# LED_Array.net
KiCad netlist of a schematic drawn in Altium Designer
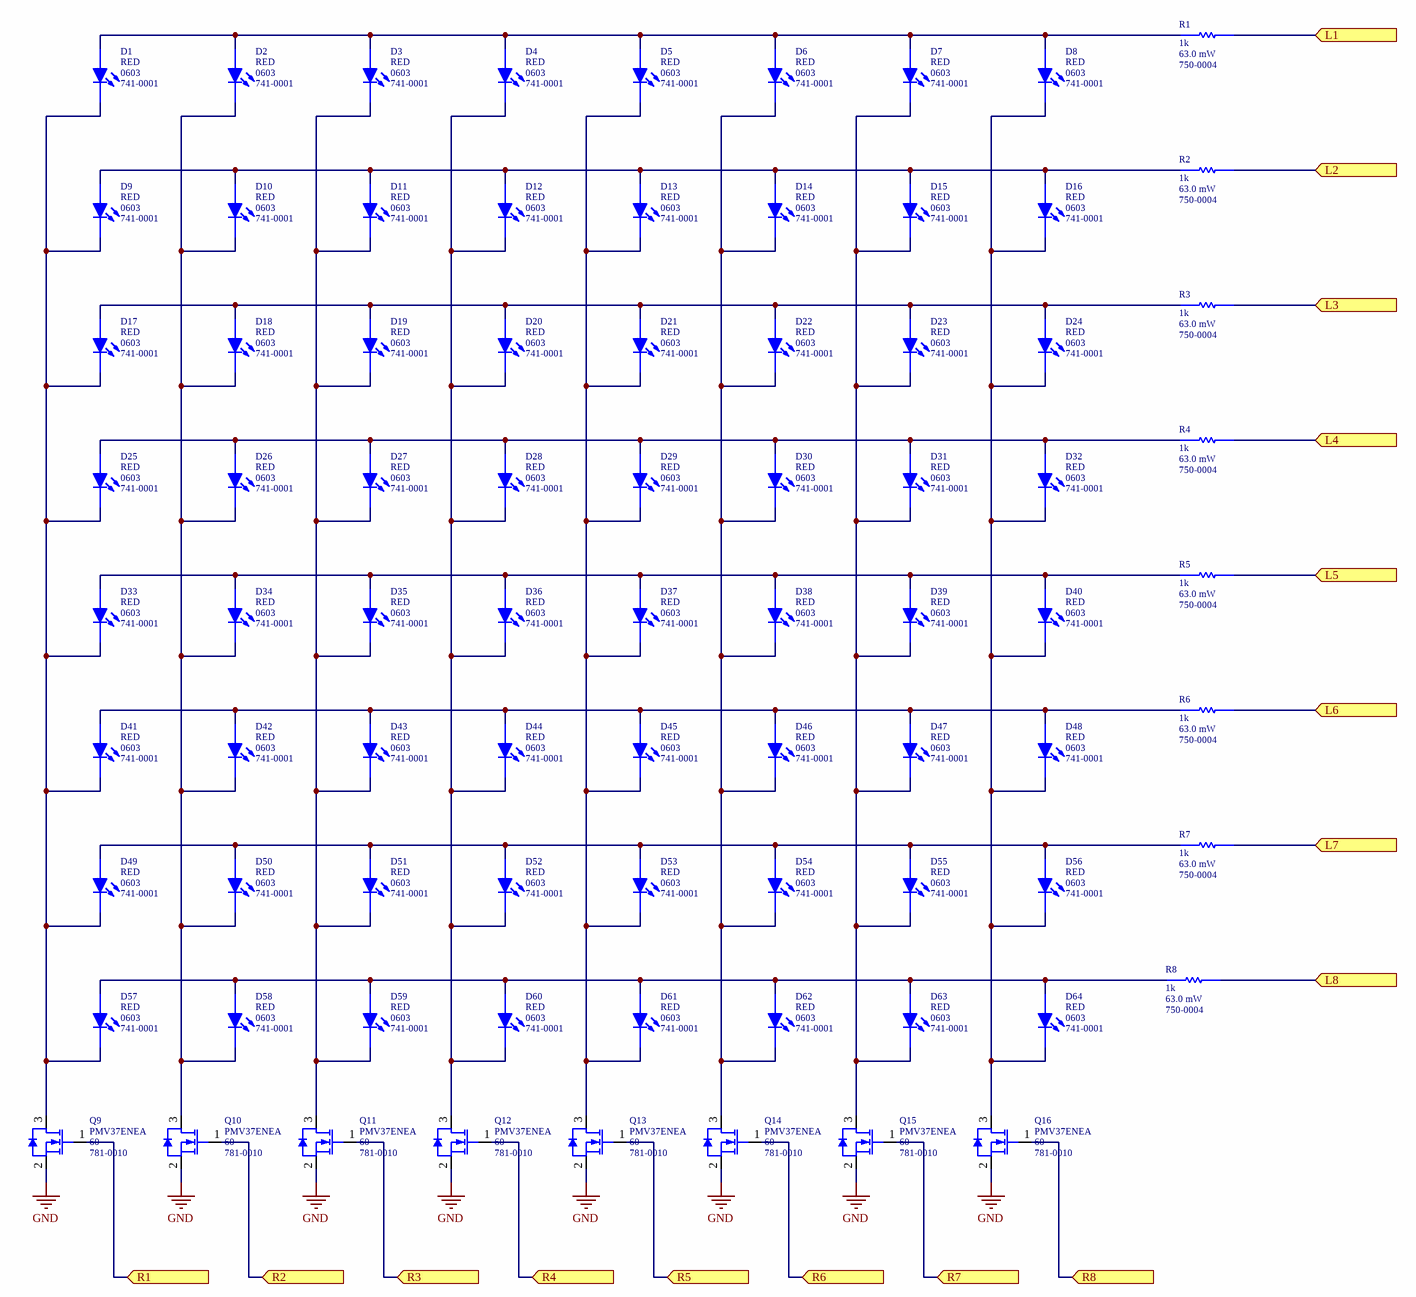
[diagram p0: LED Array.SchDoc]

(export (version "E")
  (design (tool "Eeschema 10.0.6"))
  (components
    (comp (ref "D1")
      (value "RED")
      (footprint "LED0603-IPC-MD")
      (description "LED RED 0603 2V 20mA 75mW")
      (fields
        (field (name "PACKAGE") "0603")
        (field (name "PART NUMBER") "741-0001")
        (field (name "MPN") "VLMS1300-GS08")
        (field (name "MANUFACTURER") "VISHAY")
      )
      (libsource (lib "rnlib2") (part "LED"))
    )
    (comp (ref "D2")
      (value "RED")
      (footprint "LED0603-IPC-MD")
      (description "LED RED 0603 2V 20mA 75mW")
      (fields
        (field (name "PACKAGE") "0603")
        (field (name "PART NUMBER") "741-0001")
        (field (name "MPN") "VLMS1300-GS08")
        (field (name "MANUFACTURER") "VISHAY")
      )
      (libsource (lib "rnlib2") (part "LED"))
    )
    (comp (ref "D3")
      (value "RED")
      (footprint "LED0603-IPC-MD")
      (description "LED RED 0603 2V 20mA 75mW")
      (fields
        (field (name "PACKAGE") "0603")
        (field (name "PART NUMBER") "741-0001")
        (field (name "MPN") "VLMS1300-GS08")
        (field (name "MANUFACTURER") "VISHAY")
      )
      (libsource (lib "rnlib2") (part "LED"))
    )
    (comp (ref "D4")
      (value "RED")
      (footprint "LED0603-IPC-MD")
      (description "LED RED 0603 2V 20mA 75mW")
      (fields
        (field (name "PACKAGE") "0603")
        (field (name "PART NUMBER") "741-0001")
        (field (name "MPN") "VLMS1300-GS08")
        (field (name "MANUFACTURER") "VISHAY")
      )
      (libsource (lib "rnlib2") (part "LED"))
    )
    (comp (ref "D5")
      (value "RED")
      (footprint "LED0603-IPC-MD")
      (description "LED RED 0603 2V 20mA 75mW")
      (fields
        (field (name "PACKAGE") "0603")
        (field (name "PART NUMBER") "741-0001")
        (field (name "MPN") "VLMS1300-GS08")
        (field (name "MANUFACTURER") "VISHAY")
      )
      (libsource (lib "rnlib2") (part "LED"))
    )
    (comp (ref "D6")
      (value "RED")
      (footprint "LED0603-IPC-MD")
      (description "LED RED 0603 2V 20mA 75mW")
      (fields
        (field (name "PACKAGE") "0603")
        (field (name "PART NUMBER") "741-0001")
        (field (name "MPN") "VLMS1300-GS08")
        (field (name "MANUFACTURER") "VISHAY")
      )
      (libsource (lib "rnlib2") (part "LED"))
    )
    (comp (ref "D7")
      (value "RED")
      (footprint "LED0603-IPC-MD")
      (description "LED RED 0603 2V 20mA 75mW")
      (fields
        (field (name "PACKAGE") "0603")
        (field (name "PART NUMBER") "741-0001")
        (field (name "MPN") "VLMS1300-GS08")
        (field (name "MANUFACTURER") "VISHAY")
      )
      (libsource (lib "rnlib2") (part "LED"))
    )
    (comp (ref "D8")
      (value "RED")
      (footprint "LED0603-IPC-MD")
      (description "LED RED 0603 2V 20mA 75mW")
      (fields
        (field (name "PACKAGE") "0603")
        (field (name "PART NUMBER") "741-0001")
        (field (name "MPN") "VLMS1300-GS08")
        (field (name "MANUFACTURER") "VISHAY")
      )
      (libsource (lib "rnlib2") (part "LED"))
    )
    (comp (ref "D9")
      (value "RED")
      (footprint "LED0603-IPC-MD")
      (description "LED RED 0603 2V 20mA 75mW")
      (fields
        (field (name "PACKAGE") "0603")
        (field (name "PART NUMBER") "741-0001")
        (field (name "MPN") "VLMS1300-GS08")
        (field (name "MANUFACTURER") "VISHAY")
      )
      (libsource (lib "rnlib2") (part "LED"))
    )
    (comp (ref "D10")
      (value "RED")
      (footprint "LED0603-IPC-MD")
      (description "LED RED 0603 2V 20mA 75mW")
      (fields
        (field (name "PACKAGE") "0603")
        (field (name "PART NUMBER") "741-0001")
        (field (name "MPN") "VLMS1300-GS08")
        (field (name "MANUFACTURER") "VISHAY")
      )
      (libsource (lib "rnlib2") (part "LED"))
    )
    (comp (ref "D11")
      (value "RED")
      (footprint "LED0603-IPC-MD")
      (description "LED RED 0603 2V 20mA 75mW")
      (fields
        (field (name "PACKAGE") "0603")
        (field (name "PART NUMBER") "741-0001")
        (field (name "MPN") "VLMS1300-GS08")
        (field (name "MANUFACTURER") "VISHAY")
      )
      (libsource (lib "rnlib2") (part "LED"))
    )
    (comp (ref "D12")
      (value "RED")
      (footprint "LED0603-IPC-MD")
      (description "LED RED 0603 2V 20mA 75mW")
      (fields
        (field (name "PACKAGE") "0603")
        (field (name "PART NUMBER") "741-0001")
        (field (name "MPN") "VLMS1300-GS08")
        (field (name "MANUFACTURER") "VISHAY")
      )
      (libsource (lib "rnlib2") (part "LED"))
    )
    (comp (ref "D13")
      (value "RED")
      (footprint "LED0603-IPC-MD")
      (description "LED RED 0603 2V 20mA 75mW")
      (fields
        (field (name "PACKAGE") "0603")
        (field (name "PART NUMBER") "741-0001")
        (field (name "MPN") "VLMS1300-GS08")
        (field (name "MANUFACTURER") "VISHAY")
      )
      (libsource (lib "rnlib2") (part "LED"))
    )
    (comp (ref "D14")
      (value "RED")
      (footprint "LED0603-IPC-MD")
      (description "LED RED 0603 2V 20mA 75mW")
      (fields
        (field (name "PACKAGE") "0603")
        (field (name "PART NUMBER") "741-0001")
        (field (name "MPN") "VLMS1300-GS08")
        (field (name "MANUFACTURER") "VISHAY")
      )
      (libsource (lib "rnlib2") (part "LED"))
    )
    (comp (ref "D15")
      (value "RED")
      (footprint "LED0603-IPC-MD")
      (description "LED RED 0603 2V 20mA 75mW")
      (fields
        (field (name "PACKAGE") "0603")
        (field (name "PART NUMBER") "741-0001")
        (field (name "MPN") "VLMS1300-GS08")
        (field (name "MANUFACTURER") "VISHAY")
      )
      (libsource (lib "rnlib2") (part "LED"))
    )
    (comp (ref "D16")
      (value "RED")
      (footprint "LED0603-IPC-MD")
      (description "LED RED 0603 2V 20mA 75mW")
      (fields
        (field (name "PACKAGE") "0603")
        (field (name "PART NUMBER") "741-0001")
        (field (name "MPN") "VLMS1300-GS08")
        (field (name "MANUFACTURER") "VISHAY")
      )
      (libsource (lib "rnlib2") (part "LED"))
    )
    (comp (ref "D17")
      (value "RED")
      (footprint "LED0603-IPC-MD")
      (description "LED RED 0603 2V 20mA 75mW")
      (fields
        (field (name "PACKAGE") "0603")
        (field (name "PART NUMBER") "741-0001")
        (field (name "MPN") "VLMS1300-GS08")
        (field (name "MANUFACTURER") "VISHAY")
      )
      (libsource (lib "rnlib2") (part "LED"))
    )
    (comp (ref "D18")
      (value "RED")
      (footprint "LED0603-IPC-MD")
      (description "LED RED 0603 2V 20mA 75mW")
      (fields
        (field (name "PACKAGE") "0603")
        (field (name "PART NUMBER") "741-0001")
        (field (name "MPN") "VLMS1300-GS08")
        (field (name "MANUFACTURER") "VISHAY")
      )
      (libsource (lib "rnlib2") (part "LED"))
    )
    (comp (ref "D19")
      (value "RED")
      (footprint "LED0603-IPC-MD")
      (description "LED RED 0603 2V 20mA 75mW")
      (fields
        (field (name "PACKAGE") "0603")
        (field (name "PART NUMBER") "741-0001")
        (field (name "MPN") "VLMS1300-GS08")
        (field (name "MANUFACTURER") "VISHAY")
      )
      (libsource (lib "rnlib2") (part "LED"))
    )
    (comp (ref "D20")
      (value "RED")
      (footprint "LED0603-IPC-MD")
      (description "LED RED 0603 2V 20mA 75mW")
      (fields
        (field (name "PACKAGE") "0603")
        (field (name "PART NUMBER") "741-0001")
        (field (name "MPN") "VLMS1300-GS08")
        (field (name "MANUFACTURER") "VISHAY")
      )
      (libsource (lib "rnlib2") (part "LED"))
    )
    (comp (ref "D21")
      (value "RED")
      (footprint "LED0603-IPC-MD")
      (description "LED RED 0603 2V 20mA 75mW")
      (fields
        (field (name "PACKAGE") "0603")
        (field (name "PART NUMBER") "741-0001")
        (field (name "MPN") "VLMS1300-GS08")
        (field (name "MANUFACTURER") "VISHAY")
      )
      (libsource (lib "rnlib2") (part "LED"))
    )
    (comp (ref "D22")
      (value "RED")
      (footprint "LED0603-IPC-MD")
      (description "LED RED 0603 2V 20mA 75mW")
      (fields
        (field (name "PACKAGE") "0603")
        (field (name "PART NUMBER") "741-0001")
        (field (name "MPN") "VLMS1300-GS08")
        (field (name "MANUFACTURER") "VISHAY")
      )
      (libsource (lib "rnlib2") (part "LED"))
    )
    (comp (ref "D23")
      (value "RED")
      (footprint "LED0603-IPC-MD")
      (description "LED RED 0603 2V 20mA 75mW")
      (fields
        (field (name "PACKAGE") "0603")
        (field (name "PART NUMBER") "741-0001")
        (field (name "MPN") "VLMS1300-GS08")
        (field (name "MANUFACTURER") "VISHAY")
      )
      (libsource (lib "rnlib2") (part "LED"))
    )
    (comp (ref "D24")
      (value "RED")
      (footprint "LED0603-IPC-MD")
      (description "LED RED 0603 2V 20mA 75mW")
      (fields
        (field (name "PACKAGE") "0603")
        (field (name "PART NUMBER") "741-0001")
        (field (name "MPN") "VLMS1300-GS08")
        (field (name "MANUFACTURER") "VISHAY")
      )
      (libsource (lib "rnlib2") (part "LED"))
    )
    (comp (ref "D25")
      (value "RED")
      (footprint "LED0603-IPC-MD")
      (description "LED RED 0603 2V 20mA 75mW")
      (fields
        (field (name "PACKAGE") "0603")
        (field (name "PART NUMBER") "741-0001")
        (field (name "MPN") "VLMS1300-GS08")
        (field (name "MANUFACTURER") "VISHAY")
      )
      (libsource (lib "rnlib2") (part "LED"))
    )
    (comp (ref "D26")
      (value "RED")
      (footprint "LED0603-IPC-MD")
      (description "LED RED 0603 2V 20mA 75mW")
      (fields
        (field (name "PACKAGE") "0603")
        (field (name "PART NUMBER") "741-0001")
        (field (name "MPN") "VLMS1300-GS08")
        (field (name "MANUFACTURER") "VISHAY")
      )
      (libsource (lib "rnlib2") (part "LED"))
    )
    (comp (ref "D27")
      (value "RED")
      (footprint "LED0603-IPC-MD")
      (description "LED RED 0603 2V 20mA 75mW")
      (fields
        (field (name "PACKAGE") "0603")
        (field (name "PART NUMBER") "741-0001")
        (field (name "MPN") "VLMS1300-GS08")
        (field (name "MANUFACTURER") "VISHAY")
      )
      (libsource (lib "rnlib2") (part "LED"))
    )
    (comp (ref "D28")
      (value "RED")
      (footprint "LED0603-IPC-MD")
      (description "LED RED 0603 2V 20mA 75mW")
      (fields
        (field (name "PACKAGE") "0603")
        (field (name "PART NUMBER") "741-0001")
        (field (name "MPN") "VLMS1300-GS08")
        (field (name "MANUFACTURER") "VISHAY")
      )
      (libsource (lib "rnlib2") (part "LED"))
    )
    (comp (ref "D29")
      (value "RED")
      (footprint "LED0603-IPC-MD")
      (description "LED RED 0603 2V 20mA 75mW")
      (fields
        (field (name "PACKAGE") "0603")
        (field (name "PART NUMBER") "741-0001")
        (field (name "MPN") "VLMS1300-GS08")
        (field (name "MANUFACTURER") "VISHAY")
      )
      (libsource (lib "rnlib2") (part "LED"))
    )
    (comp (ref "D30")
      (value "RED")
      (footprint "LED0603-IPC-MD")
      (description "LED RED 0603 2V 20mA 75mW")
      (fields
        (field (name "PACKAGE") "0603")
        (field (name "PART NUMBER") "741-0001")
        (field (name "MPN") "VLMS1300-GS08")
        (field (name "MANUFACTURER") "VISHAY")
      )
      (libsource (lib "rnlib2") (part "LED"))
    )
    (comp (ref "D31")
      (value "RED")
      (footprint "LED0603-IPC-MD")
      (description "LED RED 0603 2V 20mA 75mW")
      (fields
        (field (name "PACKAGE") "0603")
        (field (name "PART NUMBER") "741-0001")
        (field (name "MPN") "VLMS1300-GS08")
        (field (name "MANUFACTURER") "VISHAY")
      )
      (libsource (lib "rnlib2") (part "LED"))
    )
    (comp (ref "D32")
      (value "RED")
      (footprint "LED0603-IPC-MD")
      (description "LED RED 0603 2V 20mA 75mW")
      (fields
        (field (name "PACKAGE") "0603")
        (field (name "PART NUMBER") "741-0001")
        (field (name "MPN") "VLMS1300-GS08")
        (field (name "MANUFACTURER") "VISHAY")
      )
      (libsource (lib "rnlib2") (part "LED"))
    )
    (comp (ref "D33")
      (value "RED")
      (footprint "LED0603-IPC-MD")
      (description "LED RED 0603 2V 20mA 75mW")
      (fields
        (field (name "PACKAGE") "0603")
        (field (name "PART NUMBER") "741-0001")
        (field (name "MPN") "VLMS1300-GS08")
        (field (name "MANUFACTURER") "VISHAY")
      )
      (libsource (lib "rnlib2") (part "LED"))
    )
    (comp (ref "D34")
      (value "RED")
      (footprint "LED0603-IPC-MD")
      (description "LED RED 0603 2V 20mA 75mW")
      (fields
        (field (name "PACKAGE") "0603")
        (field (name "PART NUMBER") "741-0001")
        (field (name "MPN") "VLMS1300-GS08")
        (field (name "MANUFACTURER") "VISHAY")
      )
      (libsource (lib "rnlib2") (part "LED"))
    )
    (comp (ref "D35")
      (value "RED")
      (footprint "LED0603-IPC-MD")
      (description "LED RED 0603 2V 20mA 75mW")
      (fields
        (field (name "PACKAGE") "0603")
        (field (name "PART NUMBER") "741-0001")
        (field (name "MPN") "VLMS1300-GS08")
        (field (name "MANUFACTURER") "VISHAY")
      )
      (libsource (lib "rnlib2") (part "LED"))
    )
    (comp (ref "D36")
      (value "RED")
      (footprint "LED0603-IPC-MD")
      (description "LED RED 0603 2V 20mA 75mW")
      (fields
        (field (name "PACKAGE") "0603")
        (field (name "PART NUMBER") "741-0001")
        (field (name "MPN") "VLMS1300-GS08")
        (field (name "MANUFACTURER") "VISHAY")
      )
      (libsource (lib "rnlib2") (part "LED"))
    )
    (comp (ref "D37")
      (value "RED")
      (footprint "LED0603-IPC-MD")
      (description "LED RED 0603 2V 20mA 75mW")
      (fields
        (field (name "PACKAGE") "0603")
        (field (name "PART NUMBER") "741-0001")
        (field (name "MPN") "VLMS1300-GS08")
        (field (name "MANUFACTURER") "VISHAY")
      )
      (libsource (lib "rnlib2") (part "LED"))
    )
    (comp (ref "D38")
      (value "RED")
      (footprint "LED0603-IPC-MD")
      (description "LED RED 0603 2V 20mA 75mW")
      (fields
        (field (name "PACKAGE") "0603")
        (field (name "PART NUMBER") "741-0001")
        (field (name "MPN") "VLMS1300-GS08")
        (field (name "MANUFACTURER") "VISHAY")
      )
      (libsource (lib "rnlib2") (part "LED"))
    )
    (comp (ref "D39")
      (value "RED")
      (footprint "LED0603-IPC-MD")
      (description "LED RED 0603 2V 20mA 75mW")
      (fields
        (field (name "PACKAGE") "0603")
        (field (name "PART NUMBER") "741-0001")
        (field (name "MPN") "VLMS1300-GS08")
        (field (name "MANUFACTURER") "VISHAY")
      )
      (libsource (lib "rnlib2") (part "LED"))
    )
    (comp (ref "D40")
      (value "RED")
      (footprint "LED0603-IPC-MD")
      (description "LED RED 0603 2V 20mA 75mW")
      (fields
        (field (name "PACKAGE") "0603")
        (field (name "PART NUMBER") "741-0001")
        (field (name "MPN") "VLMS1300-GS08")
        (field (name "MANUFACTURER") "VISHAY")
      )
      (libsource (lib "rnlib2") (part "LED"))
    )
    (comp (ref "D41")
      (value "RED")
      (footprint "LED0603-IPC-MD")
      (description "LED RED 0603 2V 20mA 75mW")
      (fields
        (field (name "PACKAGE") "0603")
        (field (name "PART NUMBER") "741-0001")
        (field (name "MPN") "VLMS1300-GS08")
        (field (name "MANUFACTURER") "VISHAY")
      )
      (libsource (lib "rnlib2") (part "LED"))
    )
    (comp (ref "D42")
      (value "RED")
      (footprint "LED0603-IPC-MD")
      (description "LED RED 0603 2V 20mA 75mW")
      (fields
        (field (name "PACKAGE") "0603")
        (field (name "PART NUMBER") "741-0001")
        (field (name "MPN") "VLMS1300-GS08")
        (field (name "MANUFACTURER") "VISHAY")
      )
      (libsource (lib "rnlib2") (part "LED"))
    )
    (comp (ref "D43")
      (value "RED")
      (footprint "LED0603-IPC-MD")
      (description "LED RED 0603 2V 20mA 75mW")
      (fields
        (field (name "PACKAGE") "0603")
        (field (name "PART NUMBER") "741-0001")
        (field (name "MPN") "VLMS1300-GS08")
        (field (name "MANUFACTURER") "VISHAY")
      )
      (libsource (lib "rnlib2") (part "LED"))
    )
    (comp (ref "D44")
      (value "RED")
      (footprint "LED0603-IPC-MD")
      (description "LED RED 0603 2V 20mA 75mW")
      (fields
        (field (name "PACKAGE") "0603")
        (field (name "PART NUMBER") "741-0001")
        (field (name "MPN") "VLMS1300-GS08")
        (field (name "MANUFACTURER") "VISHAY")
      )
      (libsource (lib "rnlib2") (part "LED"))
    )
    (comp (ref "D45")
      (value "RED")
      (footprint "LED0603-IPC-MD")
      (description "LED RED 0603 2V 20mA 75mW")
      (fields
        (field (name "PACKAGE") "0603")
        (field (name "PART NUMBER") "741-0001")
        (field (name "MPN") "VLMS1300-GS08")
        (field (name "MANUFACTURER") "VISHAY")
      )
      (libsource (lib "rnlib2") (part "LED"))
    )
    (comp (ref "D46")
      (value "RED")
      (footprint "LED0603-IPC-MD")
      (description "LED RED 0603 2V 20mA 75mW")
      (fields
        (field (name "PACKAGE") "0603")
        (field (name "PART NUMBER") "741-0001")
        (field (name "MPN") "VLMS1300-GS08")
        (field (name "MANUFACTURER") "VISHAY")
      )
      (libsource (lib "rnlib2") (part "LED"))
    )
    (comp (ref "D47")
      (value "RED")
      (footprint "LED0603-IPC-MD")
      (description "LED RED 0603 2V 20mA 75mW")
      (fields
        (field (name "PACKAGE") "0603")
        (field (name "PART NUMBER") "741-0001")
        (field (name "MPN") "VLMS1300-GS08")
        (field (name "MANUFACTURER") "VISHAY")
      )
      (libsource (lib "rnlib2") (part "LED"))
    )
    (comp (ref "D48")
      (value "RED")
      (footprint "LED0603-IPC-MD")
      (description "LED RED 0603 2V 20mA 75mW")
      (fields
        (field (name "PACKAGE") "0603")
        (field (name "PART NUMBER") "741-0001")
        (field (name "MPN") "VLMS1300-GS08")
        (field (name "MANUFACTURER") "VISHAY")
      )
      (libsource (lib "rnlib2") (part "LED"))
    )
    (comp (ref "D49")
      (value "RED")
      (footprint "LED0603-IPC-MD")
      (description "LED RED 0603 2V 20mA 75mW")
      (fields
        (field (name "PACKAGE") "0603")
        (field (name "PART NUMBER") "741-0001")
        (field (name "MPN") "VLMS1300-GS08")
        (field (name "MANUFACTURER") "VISHAY")
      )
      (libsource (lib "rnlib2") (part "LED"))
    )
    (comp (ref "D50")
      (value "RED")
      (footprint "LED0603-IPC-MD")
      (description "LED RED 0603 2V 20mA 75mW")
      (fields
        (field (name "PACKAGE") "0603")
        (field (name "PART NUMBER") "741-0001")
        (field (name "MPN") "VLMS1300-GS08")
        (field (name "MANUFACTURER") "VISHAY")
      )
      (libsource (lib "rnlib2") (part "LED"))
    )
    (comp (ref "D51")
      (value "RED")
      (footprint "LED0603-IPC-MD")
      (description "LED RED 0603 2V 20mA 75mW")
      (fields
        (field (name "PACKAGE") "0603")
        (field (name "PART NUMBER") "741-0001")
        (field (name "MPN") "VLMS1300-GS08")
        (field (name "MANUFACTURER") "VISHAY")
      )
      (libsource (lib "rnlib2") (part "LED"))
    )
    (comp (ref "D52")
      (value "RED")
      (footprint "LED0603-IPC-MD")
      (description "LED RED 0603 2V 20mA 75mW")
      (fields
        (field (name "PACKAGE") "0603")
        (field (name "PART NUMBER") "741-0001")
        (field (name "MPN") "VLMS1300-GS08")
        (field (name "MANUFACTURER") "VISHAY")
      )
      (libsource (lib "rnlib2") (part "LED"))
    )
    (comp (ref "D53")
      (value "RED")
      (footprint "LED0603-IPC-MD")
      (description "LED RED 0603 2V 20mA 75mW")
      (fields
        (field (name "PACKAGE") "0603")
        (field (name "PART NUMBER") "741-0001")
        (field (name "MPN") "VLMS1300-GS08")
        (field (name "MANUFACTURER") "VISHAY")
      )
      (libsource (lib "rnlib2") (part "LED"))
    )
    (comp (ref "D54")
      (value "RED")
      (footprint "LED0603-IPC-MD")
      (description "LED RED 0603 2V 20mA 75mW")
      (fields
        (field (name "PACKAGE") "0603")
        (field (name "PART NUMBER") "741-0001")
        (field (name "MPN") "VLMS1300-GS08")
        (field (name "MANUFACTURER") "VISHAY")
      )
      (libsource (lib "rnlib2") (part "LED"))
    )
    (comp (ref "D55")
      (value "RED")
      (footprint "LED0603-IPC-MD")
      (description "LED RED 0603 2V 20mA 75mW")
      (fields
        (field (name "PACKAGE") "0603")
        (field (name "PART NUMBER") "741-0001")
        (field (name "MPN") "VLMS1300-GS08")
        (field (name "MANUFACTURER") "VISHAY")
      )
      (libsource (lib "rnlib2") (part "LED"))
    )
    (comp (ref "D56")
      (value "RED")
      (footprint "LED0603-IPC-MD")
      (description "LED RED 0603 2V 20mA 75mW")
      (fields
        (field (name "PACKAGE") "0603")
        (field (name "PART NUMBER") "741-0001")
        (field (name "MPN") "VLMS1300-GS08")
        (field (name "MANUFACTURER") "VISHAY")
      )
      (libsource (lib "rnlib2") (part "LED"))
    )
    (comp (ref "D57")
      (value "RED")
      (footprint "LED0603-IPC-MD")
      (description "LED RED 0603 2V 20mA 75mW")
      (fields
        (field (name "PACKAGE") "0603")
        (field (name "PART NUMBER") "741-0001")
        (field (name "MPN") "VLMS1300-GS08")
        (field (name "MANUFACTURER") "VISHAY")
      )
      (libsource (lib "rnlib2") (part "LED"))
    )
    (comp (ref "D58")
      (value "RED")
      (footprint "LED0603-IPC-MD")
      (description "LED RED 0603 2V 20mA 75mW")
      (fields
        (field (name "PACKAGE") "0603")
        (field (name "PART NUMBER") "741-0001")
        (field (name "MPN") "VLMS1300-GS08")
        (field (name "MANUFACTURER") "VISHAY")
      )
      (libsource (lib "rnlib2") (part "LED"))
    )
    (comp (ref "D59")
      (value "RED")
      (footprint "LED0603-IPC-MD")
      (description "LED RED 0603 2V 20mA 75mW")
      (fields
        (field (name "PACKAGE") "0603")
        (field (name "PART NUMBER") "741-0001")
        (field (name "MPN") "VLMS1300-GS08")
        (field (name "MANUFACTURER") "VISHAY")
      )
      (libsource (lib "rnlib2") (part "LED"))
    )
    (comp (ref "D60")
      (value "RED")
      (footprint "LED0603-IPC-MD")
      (description "LED RED 0603 2V 20mA 75mW")
      (fields
        (field (name "PACKAGE") "0603")
        (field (name "PART NUMBER") "741-0001")
        (field (name "MPN") "VLMS1300-GS08")
        (field (name "MANUFACTURER") "VISHAY")
      )
      (libsource (lib "rnlib2") (part "LED"))
    )
    (comp (ref "D61")
      (value "RED")
      (footprint "LED0603-IPC-MD")
      (description "LED RED 0603 2V 20mA 75mW")
      (fields
        (field (name "PACKAGE") "0603")
        (field (name "PART NUMBER") "741-0001")
        (field (name "MPN") "VLMS1300-GS08")
        (field (name "MANUFACTURER") "VISHAY")
      )
      (libsource (lib "rnlib2") (part "LED"))
    )
    (comp (ref "D62")
      (value "RED")
      (footprint "LED0603-IPC-MD")
      (description "LED RED 0603 2V 20mA 75mW")
      (fields
        (field (name "PACKAGE") "0603")
        (field (name "PART NUMBER") "741-0001")
        (field (name "MPN") "VLMS1300-GS08")
        (field (name "MANUFACTURER") "VISHAY")
      )
      (libsource (lib "rnlib2") (part "LED"))
    )
    (comp (ref "D63")
      (value "RED")
      (footprint "LED0603-IPC-MD")
      (description "LED RED 0603 2V 20mA 75mW")
      (fields
        (field (name "PACKAGE") "0603")
        (field (name "PART NUMBER") "741-0001")
        (field (name "MPN") "VLMS1300-GS08")
        (field (name "MANUFACTURER") "VISHAY")
      )
      (libsource (lib "rnlib2") (part "LED"))
    )
    (comp (ref "D64")
      (value "RED")
      (footprint "LED0603-IPC-MD")
      (description "LED RED 0603 2V 20mA 75mW")
      (fields
        (field (name "PACKAGE") "0603")
        (field (name "PART NUMBER") "741-0001")
        (field (name "MPN") "VLMS1300-GS08")
        (field (name "MANUFACTURER") "VISHAY")
      )
      (libsource (lib "rnlib2") (part "LED"))
    )
    (comp (ref "Q9")
      (value "PMV37ENEA")
      (footprint "SOT-23")
      (description "60 V, N-channel Trench MOSFET")
      (fields
        (field (name "VDS MAX") "60")
        (field (name "PART NUMBER") "781-0010")
        (field (name "MANUFACTURER") "NEXPERIA")
      )
      (libsource (lib "rnlib2") (part "FET-N-GSD"))
    )
    (comp (ref "Q10")
      (value "PMV37ENEA")
      (footprint "SOT-23")
      (description "60 V, N-channel Trench MOSFET")
      (fields
        (field (name "VDS MAX") "60")
        (field (name "PART NUMBER") "781-0010")
        (field (name "MANUFACTURER") "NEXPERIA")
      )
      (libsource (lib "rnlib2") (part "FET-N-GSD"))
    )
    (comp (ref "Q11")
      (value "PMV37ENEA")
      (footprint "SOT-23")
      (description "60 V, N-channel Trench MOSFET")
      (fields
        (field (name "VDS MAX") "60")
        (field (name "PART NUMBER") "781-0010")
        (field (name "MANUFACTURER") "NEXPERIA")
      )
      (libsource (lib "rnlib2") (part "FET-N-GSD"))
    )
    (comp (ref "Q12")
      (value "PMV37ENEA")
      (footprint "SOT-23")
      (description "60 V, N-channel Trench MOSFET")
      (fields
        (field (name "VDS MAX") "60")
        (field (name "PART NUMBER") "781-0010")
        (field (name "MANUFACTURER") "NEXPERIA")
      )
      (libsource (lib "rnlib2") (part "FET-N-GSD"))
    )
    (comp (ref "Q13")
      (value "PMV37ENEA")
      (footprint "SOT-23")
      (description "60 V, N-channel Trench MOSFET")
      (fields
        (field (name "VDS MAX") "60")
        (field (name "PART NUMBER") "781-0010")
        (field (name "MANUFACTURER") "NEXPERIA")
      )
      (libsource (lib "rnlib2") (part "FET-N-GSD"))
    )
    (comp (ref "Q14")
      (value "PMV37ENEA")
      (footprint "SOT-23")
      (description "60 V, N-channel Trench MOSFET")
      (fields
        (field (name "VDS MAX") "60")
        (field (name "PART NUMBER") "781-0010")
        (field (name "MANUFACTURER") "NEXPERIA")
      )
      (libsource (lib "rnlib2") (part "FET-N-GSD"))
    )
    (comp (ref "Q15")
      (value "PMV37ENEA")
      (footprint "SOT-23")
      (description "60 V, N-channel Trench MOSFET")
      (fields
        (field (name "VDS MAX") "60")
        (field (name "PART NUMBER") "781-0010")
        (field (name "MANUFACTURER") "NEXPERIA")
      )
      (libsource (lib "rnlib2") (part "FET-N-GSD"))
    )
    (comp (ref "Q16")
      (value "PMV37ENEA")
      (footprint "SOT-23")
      (description "60 V, N-channel Trench MOSFET")
      (fields
        (field (name "VDS MAX") "60")
        (field (name "PART NUMBER") "781-0010")
        (field (name "MANUFACTURER") "NEXPERIA")
      )
      (libsource (lib "rnlib2") (part "FET-N-GSD"))
    )
    (comp (ref "R1")
      (value "1k")
      (footprint "R0402-IPC-MD")
      (description "Resistor 1k 0402 1% 63.0 mW")
      (fields
        (field (name "PMAX") "63.0 mW")
        (field (name "PART NUMBER") "750-0004")
        (field (name "MPN") "CRCW04021K00FKED")
        (field (name "MANUFACTURER") "VISHAY")
      )
      (libsource (lib "rnlib2") (part "Resistors"))
    )
    (comp (ref "R2")
      (value "1k")
      (footprint "R0402-IPC-MD")
      (description "Resistor 1k 0402 1% 63.0 mW")
      (fields
        (field (name "PMAX") "63.0 mW")
        (field (name "PART NUMBER") "750-0004")
        (field (name "MPN") "CRCW04021K00FKED")
        (field (name "MANUFACTURER") "VISHAY")
      )
      (libsource (lib "rnlib2") (part "Resistors"))
    )
    (comp (ref "R3")
      (value "1k")
      (footprint "R0402-IPC-MD")
      (description "Resistor 1k 0402 1% 63.0 mW")
      (fields
        (field (name "PMAX") "63.0 mW")
        (field (name "PART NUMBER") "750-0004")
        (field (name "MPN") "CRCW04021K00FKED")
        (field (name "MANUFACTURER") "VISHAY")
      )
      (libsource (lib "rnlib2") (part "Resistors"))
    )
    (comp (ref "R4")
      (value "1k")
      (footprint "R0402-IPC-MD")
      (description "Resistor 1k 0402 1% 63.0 mW")
      (fields
        (field (name "PMAX") "63.0 mW")
        (field (name "PART NUMBER") "750-0004")
        (field (name "MPN") "CRCW04021K00FKED")
        (field (name "MANUFACTURER") "VISHAY")
      )
      (libsource (lib "rnlib2") (part "Resistors"))
    )
    (comp (ref "R5")
      (value "1k")
      (footprint "R0402-IPC-MD")
      (description "Resistor 1k 0402 1% 63.0 mW")
      (fields
        (field (name "PMAX") "63.0 mW")
        (field (name "PART NUMBER") "750-0004")
        (field (name "MPN") "CRCW04021K00FKED")
        (field (name "MANUFACTURER") "VISHAY")
      )
      (libsource (lib "rnlib2") (part "Resistors"))
    )
    (comp (ref "R6")
      (value "1k")
      (footprint "R0402-IPC-MD")
      (description "Resistor 1k 0402 1% 63.0 mW")
      (fields
        (field (name "PMAX") "63.0 mW")
        (field (name "PART NUMBER") "750-0004")
        (field (name "MPN") "CRCW04021K00FKED")
        (field (name "MANUFACTURER") "VISHAY")
      )
      (libsource (lib "rnlib2") (part "Resistors"))
    )
    (comp (ref "R7")
      (value "1k")
      (footprint "R0402-IPC-MD")
      (description "Resistor 1k 0402 1% 63.0 mW")
      (fields
        (field (name "PMAX") "63.0 mW")
        (field (name "PART NUMBER") "750-0004")
        (field (name "MPN") "CRCW04021K00FKED")
        (field (name "MANUFACTURER") "VISHAY")
      )
      (libsource (lib "rnlib2") (part "Resistors"))
    )
    (comp (ref "R8")
      (value "1k")
      (footprint "R0402-IPC-MD")
      (description "Resistor 1k 0402 1% 63.0 mW")
      (fields
        (field (name "PMAX") "63.0 mW")
        (field (name "PART NUMBER") "750-0004")
        (field (name "MPN") "CRCW04021K00FKED")
        (field (name "MANUFACTURER") "VISHAY")
      )
      (libsource (lib "rnlib2") (part "Resistors"))
    )
  )
  (nets
    (net (code "1") (name "/L1") (class "Default")
      (node (ref "R1") (pin "2") (pinfunction "2_2") (pintype "passive"))
    )
    (net (code "2") (name "/L2") (class "Default")
      (node (ref "R2") (pin "2") (pinfunction "2_2") (pintype "passive"))
    )
    (net (code "3") (name "/L3") (class "Default")
      (node (ref "R3") (pin "2") (pinfunction "2_2") (pintype "passive"))
    )
    (net (code "4") (name "/L4") (class "Default")
      (node (ref "R4") (pin "2") (pinfunction "2_2") (pintype "passive"))
    )
    (net (code "5") (name "/L5") (class "Default")
      (node (ref "R5") (pin "2") (pinfunction "2_2") (pintype "passive"))
    )
    (net (code "6") (name "/L6") (class "Default")
      (node (ref "R6") (pin "2") (pinfunction "2_2") (pintype "passive"))
    )
    (net (code "7") (name "/L7") (class "Default")
      (node (ref "R7") (pin "2") (pinfunction "2_2") (pintype "passive"))
    )
    (net (code "8") (name "/L8") (class "Default")
      (node (ref "R8") (pin "2") (pinfunction "2_2") (pintype "passive"))
    )
    (net (code "9") (name "/R1") (class "Default")
      (node (ref "Q9") (pin "1") (pinfunction "G_1") (pintype "passive"))
    )
    (net (code "10") (name "/R2") (class "Default")
      (node (ref "Q10") (pin "1") (pinfunction "G_1") (pintype "passive"))
    )
    (net (code "11") (name "/R3") (class "Default")
      (node (ref "Q11") (pin "1") (pinfunction "G_1") (pintype "passive"))
    )
    (net (code "12") (name "/R4") (class "Default")
      (node (ref "Q12") (pin "1") (pinfunction "G_1") (pintype "passive"))
    )
    (net (code "13") (name "/R5") (class "Default")
      (node (ref "Q13") (pin "1") (pinfunction "G_1") (pintype "passive"))
    )
    (net (code "14") (name "/R6") (class "Default")
      (node (ref "Q14") (pin "1") (pinfunction "G_1") (pintype "passive"))
    )
    (net (code "15") (name "/R7") (class "Default")
      (node (ref "Q15") (pin "1") (pinfunction "G_1") (pintype "passive"))
    )
    (net (code "16") (name "/R8") (class "Default")
      (node (ref "Q16") (pin "1") (pinfunction "G_1") (pintype "passive"))
    )
    (net (code "17") (name "GND") (class "Default")
      (node (ref "Q10") (pin "2") (pinfunction "S_2") (pintype "passive"))
      (node (ref "Q11") (pin "2") (pinfunction "S_2") (pintype "passive"))
      (node (ref "Q12") (pin "2") (pinfunction "S_2") (pintype "passive"))
      (node (ref "Q13") (pin "2") (pinfunction "S_2") (pintype "passive"))
      (node (ref "Q14") (pin "2") (pinfunction "S_2") (pintype "passive"))
      (node (ref "Q15") (pin "2") (pinfunction "S_2") (pintype "passive"))
      (node (ref "Q16") (pin "2") (pinfunction "S_2") (pintype "passive"))
      (node (ref "Q9") (pin "2") (pinfunction "S_2") (pintype "passive"))
    )
    (net (code "18") (name "Net-(D1-A)") (class "Default")
      (node (ref "D1") (pin "2") (pinfunction "A_2") (pintype "passive"))
      (node (ref "D2") (pin "2") (pinfunction "A_2") (pintype "passive"))
      (node (ref "D3") (pin "2") (pinfunction "A_2") (pintype "passive"))
      (node (ref "D4") (pin "2") (pinfunction "A_2") (pintype "passive"))
      (node (ref "D5") (pin "2") (pinfunction "A_2") (pintype "passive"))
      (node (ref "D6") (pin "2") (pinfunction "A_2") (pintype "passive"))
      (node (ref "D7") (pin "2") (pinfunction "A_2") (pintype "passive"))
      (node (ref "D8") (pin "2") (pinfunction "A_2") (pintype "passive"))
      (node (ref "R1") (pin "1") (pinfunction "1_1") (pintype "passive"))
    )
    (net (code "19") (name "Net-(D1-K)") (class "Default")
      (node (ref "D1") (pin "1") (pinfunction "K_1") (pintype "passive"))
      (node (ref "D17") (pin "1") (pinfunction "K_1") (pintype "passive"))
      (node (ref "D25") (pin "1") (pinfunction "K_1") (pintype "passive"))
      (node (ref "D33") (pin "1") (pinfunction "K_1") (pintype "passive"))
      (node (ref "D41") (pin "1") (pinfunction "K_1") (pintype "passive"))
      (node (ref "D49") (pin "1") (pinfunction "K_1") (pintype "passive"))
      (node (ref "D57") (pin "1") (pinfunction "K_1") (pintype "passive"))
      (node (ref "D9") (pin "1") (pinfunction "K_1") (pintype "passive"))
      (node (ref "Q9") (pin "3") (pinfunction "D_3") (pintype "passive"))
    )
    (net (code "20") (name "Net-(D10-A)") (class "Default")
      (node (ref "D10") (pin "2") (pinfunction "A_2") (pintype "passive"))
      (node (ref "D11") (pin "2") (pinfunction "A_2") (pintype "passive"))
      (node (ref "D12") (pin "2") (pinfunction "A_2") (pintype "passive"))
      (node (ref "D13") (pin "2") (pinfunction "A_2") (pintype "passive"))
      (node (ref "D14") (pin "2") (pinfunction "A_2") (pintype "passive"))
      (node (ref "D15") (pin "2") (pinfunction "A_2") (pintype "passive"))
      (node (ref "D16") (pin "2") (pinfunction "A_2") (pintype "passive"))
      (node (ref "D9") (pin "2") (pinfunction "A_2") (pintype "passive"))
      (node (ref "R2") (pin "1") (pinfunction "1_1") (pintype "passive"))
    )
    (net (code "21") (name "Net-(D10-K)") (class "Default")
      (node (ref "D10") (pin "1") (pinfunction "K_1") (pintype "passive"))
      (node (ref "D18") (pin "1") (pinfunction "K_1") (pintype "passive"))
      (node (ref "D2") (pin "1") (pinfunction "K_1") (pintype "passive"))
      (node (ref "D26") (pin "1") (pinfunction "K_1") (pintype "passive"))
      (node (ref "D34") (pin "1") (pinfunction "K_1") (pintype "passive"))
      (node (ref "D42") (pin "1") (pinfunction "K_1") (pintype "passive"))
      (node (ref "D50") (pin "1") (pinfunction "K_1") (pintype "passive"))
      (node (ref "D58") (pin "1") (pinfunction "K_1") (pintype "passive"))
      (node (ref "Q10") (pin "3") (pinfunction "D_3") (pintype "passive"))
    )
    (net (code "22") (name "Net-(D11-K)") (class "Default")
      (node (ref "D11") (pin "1") (pinfunction "K_1") (pintype "passive"))
      (node (ref "D19") (pin "1") (pinfunction "K_1") (pintype "passive"))
      (node (ref "D27") (pin "1") (pinfunction "K_1") (pintype "passive"))
      (node (ref "D3") (pin "1") (pinfunction "K_1") (pintype "passive"))
      (node (ref "D35") (pin "1") (pinfunction "K_1") (pintype "passive"))
      (node (ref "D43") (pin "1") (pinfunction "K_1") (pintype "passive"))
      (node (ref "D51") (pin "1") (pinfunction "K_1") (pintype "passive"))
      (node (ref "D59") (pin "1") (pinfunction "K_1") (pintype "passive"))
      (node (ref "Q11") (pin "3") (pinfunction "D_3") (pintype "passive"))
    )
    (net (code "23") (name "Net-(D12-K)") (class "Default")
      (node (ref "D12") (pin "1") (pinfunction "K_1") (pintype "passive"))
      (node (ref "D20") (pin "1") (pinfunction "K_1") (pintype "passive"))
      (node (ref "D28") (pin "1") (pinfunction "K_1") (pintype "passive"))
      (node (ref "D36") (pin "1") (pinfunction "K_1") (pintype "passive"))
      (node (ref "D4") (pin "1") (pinfunction "K_1") (pintype "passive"))
      (node (ref "D44") (pin "1") (pinfunction "K_1") (pintype "passive"))
      (node (ref "D52") (pin "1") (pinfunction "K_1") (pintype "passive"))
      (node (ref "D60") (pin "1") (pinfunction "K_1") (pintype "passive"))
      (node (ref "Q12") (pin "3") (pinfunction "D_3") (pintype "passive"))
    )
    (net (code "24") (name "Net-(D13-K)") (class "Default")
      (node (ref "D13") (pin "1") (pinfunction "K_1") (pintype "passive"))
      (node (ref "D21") (pin "1") (pinfunction "K_1") (pintype "passive"))
      (node (ref "D29") (pin "1") (pinfunction "K_1") (pintype "passive"))
      (node (ref "D37") (pin "1") (pinfunction "K_1") (pintype "passive"))
      (node (ref "D45") (pin "1") (pinfunction "K_1") (pintype "passive"))
      (node (ref "D5") (pin "1") (pinfunction "K_1") (pintype "passive"))
      (node (ref "D53") (pin "1") (pinfunction "K_1") (pintype "passive"))
      (node (ref "D61") (pin "1") (pinfunction "K_1") (pintype "passive"))
      (node (ref "Q13") (pin "3") (pinfunction "D_3") (pintype "passive"))
    )
    (net (code "25") (name "Net-(D14-K)") (class "Default")
      (node (ref "D14") (pin "1") (pinfunction "K_1") (pintype "passive"))
      (node (ref "D22") (pin "1") (pinfunction "K_1") (pintype "passive"))
      (node (ref "D30") (pin "1") (pinfunction "K_1") (pintype "passive"))
      (node (ref "D38") (pin "1") (pinfunction "K_1") (pintype "passive"))
      (node (ref "D46") (pin "1") (pinfunction "K_1") (pintype "passive"))
      (node (ref "D54") (pin "1") (pinfunction "K_1") (pintype "passive"))
      (node (ref "D6") (pin "1") (pinfunction "K_1") (pintype "passive"))
      (node (ref "D62") (pin "1") (pinfunction "K_1") (pintype "passive"))
      (node (ref "Q14") (pin "3") (pinfunction "D_3") (pintype "passive"))
    )
    (net (code "26") (name "Net-(D15-K)") (class "Default")
      (node (ref "D15") (pin "1") (pinfunction "K_1") (pintype "passive"))
      (node (ref "D23") (pin "1") (pinfunction "K_1") (pintype "passive"))
      (node (ref "D31") (pin "1") (pinfunction "K_1") (pintype "passive"))
      (node (ref "D39") (pin "1") (pinfunction "K_1") (pintype "passive"))
      (node (ref "D47") (pin "1") (pinfunction "K_1") (pintype "passive"))
      (node (ref "D55") (pin "1") (pinfunction "K_1") (pintype "passive"))
      (node (ref "D63") (pin "1") (pinfunction "K_1") (pintype "passive"))
      (node (ref "D7") (pin "1") (pinfunction "K_1") (pintype "passive"))
      (node (ref "Q15") (pin "3") (pinfunction "D_3") (pintype "passive"))
    )
    (net (code "27") (name "Net-(D16-K)") (class "Default")
      (node (ref "D16") (pin "1") (pinfunction "K_1") (pintype "passive"))
      (node (ref "D24") (pin "1") (pinfunction "K_1") (pintype "passive"))
      (node (ref "D32") (pin "1") (pinfunction "K_1") (pintype "passive"))
      (node (ref "D40") (pin "1") (pinfunction "K_1") (pintype "passive"))
      (node (ref "D48") (pin "1") (pinfunction "K_1") (pintype "passive"))
      (node (ref "D56") (pin "1") (pinfunction "K_1") (pintype "passive"))
      (node (ref "D64") (pin "1") (pinfunction "K_1") (pintype "passive"))
      (node (ref "D8") (pin "1") (pinfunction "K_1") (pintype "passive"))
      (node (ref "Q16") (pin "3") (pinfunction "D_3") (pintype "passive"))
    )
    (net (code "28") (name "Net-(D17-A)") (class "Default")
      (node (ref "D17") (pin "2") (pinfunction "A_2") (pintype "passive"))
      (node (ref "D18") (pin "2") (pinfunction "A_2") (pintype "passive"))
      (node (ref "D19") (pin "2") (pinfunction "A_2") (pintype "passive"))
      (node (ref "D20") (pin "2") (pinfunction "A_2") (pintype "passive"))
      (node (ref "D21") (pin "2") (pinfunction "A_2") (pintype "passive"))
      (node (ref "D22") (pin "2") (pinfunction "A_2") (pintype "passive"))
      (node (ref "D23") (pin "2") (pinfunction "A_2") (pintype "passive"))
      (node (ref "D24") (pin "2") (pinfunction "A_2") (pintype "passive"))
      (node (ref "R3") (pin "1") (pinfunction "1_1") (pintype "passive"))
    )
    (net (code "29") (name "Net-(D25-A)") (class "Default")
      (node (ref "D25") (pin "2") (pinfunction "A_2") (pintype "passive"))
      (node (ref "D26") (pin "2") (pinfunction "A_2") (pintype "passive"))
      (node (ref "D27") (pin "2") (pinfunction "A_2") (pintype "passive"))
      (node (ref "D28") (pin "2") (pinfunction "A_2") (pintype "passive"))
      (node (ref "D29") (pin "2") (pinfunction "A_2") (pintype "passive"))
      (node (ref "D30") (pin "2") (pinfunction "A_2") (pintype "passive"))
      (node (ref "D31") (pin "2") (pinfunction "A_2") (pintype "passive"))
      (node (ref "D32") (pin "2") (pinfunction "A_2") (pintype "passive"))
      (node (ref "R4") (pin "1") (pinfunction "1_1") (pintype "passive"))
    )
    (net (code "30") (name "Net-(D33-A)") (class "Default")
      (node (ref "D33") (pin "2") (pinfunction "A_2") (pintype "passive"))
      (node (ref "D34") (pin "2") (pinfunction "A_2") (pintype "passive"))
      (node (ref "D35") (pin "2") (pinfunction "A_2") (pintype "passive"))
      (node (ref "D36") (pin "2") (pinfunction "A_2") (pintype "passive"))
      (node (ref "D37") (pin "2") (pinfunction "A_2") (pintype "passive"))
      (node (ref "D38") (pin "2") (pinfunction "A_2") (pintype "passive"))
      (node (ref "D39") (pin "2") (pinfunction "A_2") (pintype "passive"))
      (node (ref "D40") (pin "2") (pinfunction "A_2") (pintype "passive"))
      (node (ref "R5") (pin "1") (pinfunction "1_1") (pintype "passive"))
    )
    (net (code "31") (name "Net-(D41-A)") (class "Default")
      (node (ref "D41") (pin "2") (pinfunction "A_2") (pintype "passive"))
      (node (ref "D42") (pin "2") (pinfunction "A_2") (pintype "passive"))
      (node (ref "D43") (pin "2") (pinfunction "A_2") (pintype "passive"))
      (node (ref "D44") (pin "2") (pinfunction "A_2") (pintype "passive"))
      (node (ref "D45") (pin "2") (pinfunction "A_2") (pintype "passive"))
      (node (ref "D46") (pin "2") (pinfunction "A_2") (pintype "passive"))
      (node (ref "D47") (pin "2") (pinfunction "A_2") (pintype "passive"))
      (node (ref "D48") (pin "2") (pinfunction "A_2") (pintype "passive"))
      (node (ref "R6") (pin "1") (pinfunction "1_1") (pintype "passive"))
    )
    (net (code "32") (name "Net-(D49-A)") (class "Default")
      (node (ref "D49") (pin "2") (pinfunction "A_2") (pintype "passive"))
      (node (ref "D50") (pin "2") (pinfunction "A_2") (pintype "passive"))
      (node (ref "D51") (pin "2") (pinfunction "A_2") (pintype "passive"))
      (node (ref "D52") (pin "2") (pinfunction "A_2") (pintype "passive"))
      (node (ref "D53") (pin "2") (pinfunction "A_2") (pintype "passive"))
      (node (ref "D54") (pin "2") (pinfunction "A_2") (pintype "passive"))
      (node (ref "D55") (pin "2") (pinfunction "A_2") (pintype "passive"))
      (node (ref "D56") (pin "2") (pinfunction "A_2") (pintype "passive"))
      (node (ref "R7") (pin "1") (pinfunction "1_1") (pintype "passive"))
    )
    (net (code "33") (name "Net-(D57-A)") (class "Default")
      (node (ref "D57") (pin "2") (pinfunction "A_2") (pintype "passive"))
      (node (ref "D58") (pin "2") (pinfunction "A_2") (pintype "passive"))
      (node (ref "D59") (pin "2") (pinfunction "A_2") (pintype "passive"))
      (node (ref "D60") (pin "2") (pinfunction "A_2") (pintype "passive"))
      (node (ref "D61") (pin "2") (pinfunction "A_2") (pintype "passive"))
      (node (ref "D62") (pin "2") (pinfunction "A_2") (pintype "passive"))
      (node (ref "D63") (pin "2") (pinfunction "A_2") (pintype "passive"))
      (node (ref "D64") (pin "2") (pinfunction "A_2") (pintype "passive"))
      (node (ref "R8") (pin "1") (pinfunction "1_1") (pintype "passive"))
    )
  )
)
